# LockIn.net
KiCad netlist of a schematic drawn in Altium Designer
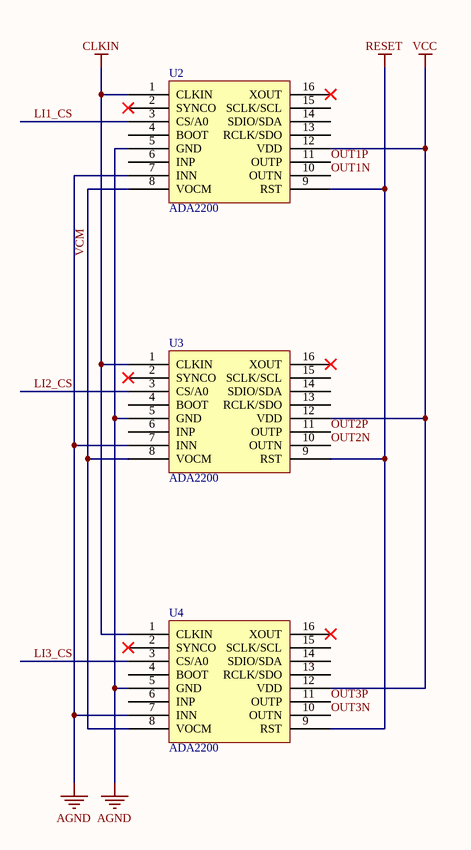
[diagram p0: LockIn.SchDoc]

(export (version "E")
  (design (tool "Eeschema 10.0.6"))
  (components
    (comp (ref "U2") (value "ADA2200") (footprint "TSSOP-16") (libsource (lib "OSA") (part "ADA2200")))
    (comp (ref "U3") (value "ADA2200") (footprint "TSSOP-16") (libsource (lib "OSA") (part "ADA2200")))
    (comp (ref "U4") (value "ADA2200") (footprint "TSSOP-16") (libsource (lib "OSA") (part "ADA2200")))
  )
  (nets
    (net (code "1") (name "/LI1_CS") (class "Default")
      (node (ref "U2") (pin "3") (pinfunction "CS/A0_3") (pintype "passive"))
    )
    (net (code "2") (name "/LI2_CS") (class "Default")
      (node (ref "U3") (pin "3") (pinfunction "CS/A0_3") (pintype "passive"))
    )
    (net (code "3") (name "/LI3_CS") (class "Default")
      (node (ref "U4") (pin "3") (pinfunction "CS/A0_3") (pintype "passive"))
    )
    (net (code "4") (name "/OUT1N") (class "Default")
      (node (ref "U2") (pin "10") (pinfunction "OUTN_10") (pintype "passive"))
    )
    (net (code "5") (name "/OUT1P") (class "Default")
      (node (ref "U2") (pin "11") (pinfunction "OUTP_11") (pintype "passive"))
    )
    (net (code "6") (name "/OUT2N") (class "Default")
      (node (ref "U3") (pin "10") (pinfunction "OUTN_10") (pintype "passive"))
    )
    (net (code "7") (name "/OUT2P") (class "Default")
      (node (ref "U3") (pin "11") (pinfunction "OUTP_11") (pintype "passive"))
    )
    (net (code "8") (name "/OUT3N") (class "Default")
      (node (ref "U4") (pin "10") (pinfunction "OUTN_10") (pintype "passive"))
    )
    (net (code "9") (name "/OUT3P") (class "Default")
      (node (ref "U4") (pin "11") (pinfunction "OUTP_11") (pintype "passive"))
    )
    (net (code "10") (name "/VCM") (class "Default")
      (node (ref "U2") (pin "8") (pinfunction "VOCM_8") (pintype "passive"))
      (node (ref "U3") (pin "8") (pinfunction "VOCM_8") (pintype "passive"))
      (node (ref "U4") (pin "8") (pinfunction "VOCM_8") (pintype "passive"))
    )
    (net (code "11") (name "AGND") (class "Default")
      (node (ref "U2") (pin "5") (pinfunction "GND_5") (pintype "passive"))
      (node (ref "U2") (pin "7") (pinfunction "INN_7") (pintype "passive"))
      (node (ref "U3") (pin "5") (pinfunction "GND_5") (pintype "passive"))
      (node (ref "U3") (pin "7") (pinfunction "INN_7") (pintype "passive"))
      (node (ref "U4") (pin "5") (pinfunction "GND_5") (pintype "passive"))
      (node (ref "U4") (pin "7") (pinfunction "INN_7") (pintype "passive"))
    )
    (net (code "12") (name "CLKIN") (class "Default")
      (node (ref "U2") (pin "1") (pinfunction "CLKIN_1") (pintype "passive"))
      (node (ref "U3") (pin "1") (pinfunction "CLKIN_1") (pintype "passive"))
      (node (ref "U4") (pin "1") (pinfunction "CLKIN_1") (pintype "passive"))
    )
    (net (code "13") (name "RESET") (class "Default")
      (node (ref "U2") (pin "9") (pinfunction "RST_9") (pintype "passive"))
      (node (ref "U3") (pin "9") (pinfunction "RST_9") (pintype "passive"))
      (node (ref "U4") (pin "9") (pinfunction "RST_9") (pintype "passive"))
    )
    (net (code "14") (name "VCC") (class "Default")
      (node (ref "U2") (pin "12") (pinfunction "VDD_12") (pintype "passive"))
      (node (ref "U3") (pin "12") (pinfunction "VDD_12") (pintype "passive"))
      (node (ref "U4") (pin "12") (pinfunction "VDD_12") (pintype "passive"))
    )
    (net (code "15") (name "unconnected-(U2-BOOT-Pad4)") (class "Default")
      (node (ref "U2") (pin "4") (pinfunction "BOOT_4") (pintype "passive"))
    )
    (net (code "16") (name "unconnected-(U2-INP-Pad6)") (class "Default")
      (node (ref "U2") (pin "6") (pinfunction "INP_6") (pintype "passive"))
    )
    (net (code "17") (name "unconnected-(U2-RCLK{slash}SDO-Pad13)") (class "Default")
      (node (ref "U2") (pin "13") (pinfunction "RCLK/SDO_13") (pintype "passive"))
    )
    (net (code "18") (name "unconnected-(U2-SCLK{slash}SCL-Pad15)") (class "Default")
      (node (ref "U2") (pin "15") (pinfunction "SCLK/SCL_15") (pintype "passive"))
    )
    (net (code "19") (name "unconnected-(U2-SDIO{slash}SDA-Pad14)") (class "Default")
      (node (ref "U2") (pin "14") (pinfunction "SDIO/SDA_14") (pintype "passive"))
    )
    (net (code "20") (name "unconnected-(U2-SYNCO-Pad2)") (class "Default")
      (node (ref "U2") (pin "2") (pinfunction "SYNCO_2") (pintype "passive+no_connect"))
    )
    (net (code "21") (name "unconnected-(U2-XOUT-Pad16)") (class "Default")
      (node (ref "U2") (pin "16") (pinfunction "XOUT_16") (pintype "passive+no_connect"))
    )
    (net (code "22") (name "unconnected-(U3-BOOT-Pad4)") (class "Default")
      (node (ref "U3") (pin "4") (pinfunction "BOOT_4") (pintype "passive"))
    )
    (net (code "23") (name "unconnected-(U3-INP-Pad6)") (class "Default")
      (node (ref "U3") (pin "6") (pinfunction "INP_6") (pintype "passive"))
    )
    (net (code "24") (name "unconnected-(U3-RCLK{slash}SDO-Pad13)") (class "Default")
      (node (ref "U3") (pin "13") (pinfunction "RCLK/SDO_13") (pintype "passive"))
    )
    (net (code "25") (name "unconnected-(U3-SCLK{slash}SCL-Pad15)") (class "Default")
      (node (ref "U3") (pin "15") (pinfunction "SCLK/SCL_15") (pintype "passive"))
    )
    (net (code "26") (name "unconnected-(U3-SDIO{slash}SDA-Pad14)") (class "Default")
      (node (ref "U3") (pin "14") (pinfunction "SDIO/SDA_14") (pintype "passive"))
    )
    (net (code "27") (name "unconnected-(U3-SYNCO-Pad2)") (class "Default")
      (node (ref "U3") (pin "2") (pinfunction "SYNCO_2") (pintype "passive+no_connect"))
    )
    (net (code "28") (name "unconnected-(U3-XOUT-Pad16)") (class "Default")
      (node (ref "U3") (pin "16") (pinfunction "XOUT_16") (pintype "passive+no_connect"))
    )
    (net (code "29") (name "unconnected-(U4-BOOT-Pad4)") (class "Default")
      (node (ref "U4") (pin "4") (pinfunction "BOOT_4") (pintype "passive"))
    )
    (net (code "30") (name "unconnected-(U4-INP-Pad6)") (class "Default")
      (node (ref "U4") (pin "6") (pinfunction "INP_6") (pintype "passive"))
    )
    (net (code "31") (name "unconnected-(U4-RCLK{slash}SDO-Pad13)") (class "Default")
      (node (ref "U4") (pin "13") (pinfunction "RCLK/SDO_13") (pintype "passive"))
    )
    (net (code "32") (name "unconnected-(U4-SCLK{slash}SCL-Pad15)") (class "Default")
      (node (ref "U4") (pin "15") (pinfunction "SCLK/SCL_15") (pintype "passive"))
    )
    (net (code "33") (name "unconnected-(U4-SDIO{slash}SDA-Pad14)") (class "Default")
      (node (ref "U4") (pin "14") (pinfunction "SDIO/SDA_14") (pintype "passive"))
    )
    (net (code "34") (name "unconnected-(U4-SYNCO-Pad2)") (class "Default")
      (node (ref "U4") (pin "2") (pinfunction "SYNCO_2") (pintype "passive+no_connect"))
    )
    (net (code "35") (name "unconnected-(U4-XOUT-Pad16)") (class "Default")
      (node (ref "U4") (pin "16") (pinfunction "XOUT_16") (pintype "passive+no_connect"))
    )
  )
)
